# Sensor_Box_PWR_DC.net
KiCad netlist of a schematic drawn in Altium Designer
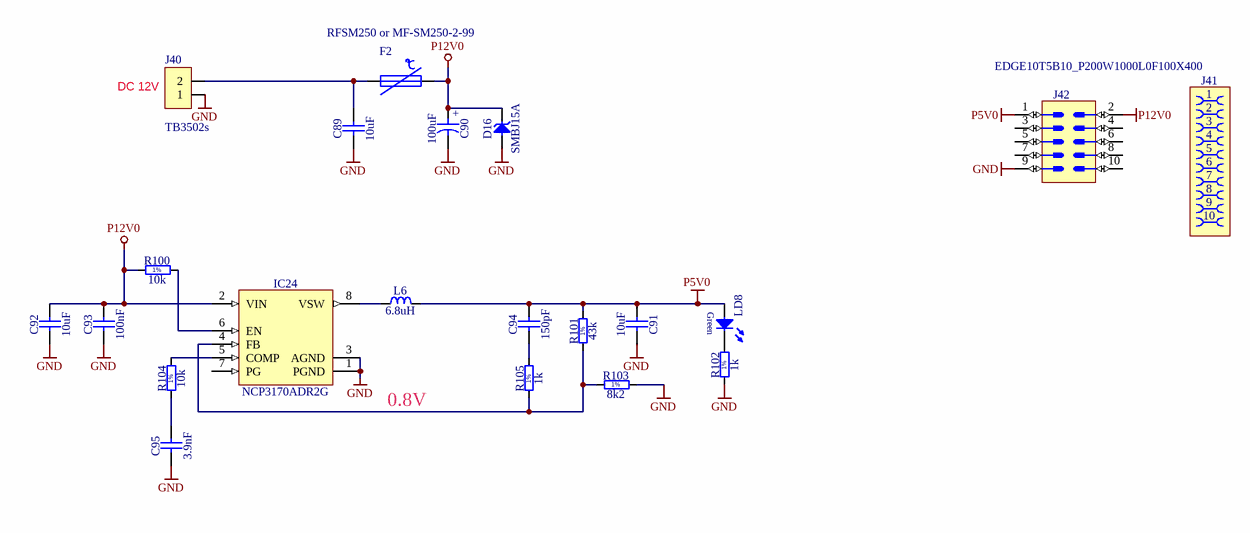
[diagram p0: Sensor_Box_PWR_DC.SchDoc]

(export (version "E")
  (design (tool "Eeschema 10.0.6"))
  (components
    (comp (ref "C89")
      (value "10uF")
      (footprint "CAPC2012X135N")
      (description "Non-polarised capacitor")
      (fields
        (field (name "PART NUMBER") "CC0805_10UF_16V_10%_X5R")
        (field (name "VOLTAGE") "16V")
        (field (name "AUTHOR") "CERN DEM JLC")
      )
      (libsource (lib "Capacitors") (part "Capacitor - non polarized"))
    )
    (comp (ref "C90")
      (value "100uF")
      (footprint "CAPAE660X540N")
      (description "Polarised capacitor")
      (fields
        (field (name "PART NUMBER") "CAE660-540_100UF_16V_20%")
        (field (name "VOLTAGE") "16V")
        (field (name "AUTHOR") "CERN DEM JLC")
      )
      (libsource (lib "Capacitors") (part "Capacitor - polarized"))
    )
    (comp (ref "C91")
      (value "10uF")
      (footprint "CAPC2012X135N")
      (description "Non-polarised capacitor")
      (fields
        (field (name "PART NUMBER") "CC0805_10UF_16V_10%_X5R")
        (field (name "VOLTAGE") "16V")
        (field (name "AUTHOR") "CERN DEM JLC")
      )
      (libsource (lib "Capacitors") (part "Capacitor - non polarized"))
    )
    (comp (ref "C92")
      (value "10uF")
      (footprint "CAPC2012X135N")
      (description "Non-polarised capacitor")
      (fields
        (field (name "PART NUMBER") "CC0805_10UF_16V_10%_X5R")
        (field (name "VOLTAGE") "16V")
        (field (name "AUTHOR") "CERN DEM JLC")
      )
      (libsource (lib "Capacitors") (part "Capacitor - non polarized"))
    )
    (comp (ref "C93")
      (value "100nF")
      (footprint "CAPC1005X55N")
      (description "Non-polarised capacitor")
      (fields
        (field (name "PART NUMBER") "CC0402_100NF_16V_10%_X5R")
        (field (name "VOLTAGE") "16V")
        (field (name "AUTHOR") "CERN DEM JLC")
      )
      (libsource (lib "Capacitors") (part "Capacitor - non polarized"))
    )
    (comp (ref "C94")
      (value "150pF")
      (footprint "CAPC1608X87N")
      (description "Non-polarised capacitor")
      (fields
        (field (name "PART NUMBER") "CC0603_150PF_50V_1%_NP0")
        (field (name "VOLTAGE") "50V")
        (field (name "AUTHOR") "CERN DEM MR")
      )
      (libsource (lib "Capacitors") (part "Capacitor - non polarized"))
    )
    (comp (ref "C95")
      (value "3.9nF")
      (footprint "CAPC1608X87N")
      (description "Non-polarised capacitor")
      (fields
        (field (name "PART NUMBER") "CC0603_3.9NF_50V_5%_X7R")
        (field (name "VOLTAGE") "50V")
        (field (name "AUTHOR") "CERN DEM JLC")
      )
      (libsource (lib "Capacitors") (part "Capacitor - non polarized"))
    )
    (comp (ref "D16")
      (value "SMBJ15A")
      (footprint "DIOM5336X265N")
      (description "Zener Diode")
      (fields
        (field (name "VOLTAGE") "15V")
        (field (name "POWER") "600W")
        (field (name "AUTHOR") "CERN DEM JLC")
      )
      (libsource (lib "ICs And Semiconductors") (part "Diode Zener"))
    )
    (comp (ref "F2")
      (value "RFSM250 or MF-SM250-2-99")
      (footprint "SMD150-2")
      (description "2.50A/15V")
      (libsource (lib "LIBRARY_SCH") (part "F_PTC_9.5x6mm"))
    )
    (comp (ref "IC24")
      (value "NCP3170ADR2G")
      (footprint "SOIC127P600X175-8N")
      (description "Synchronous PWM Switching Converter")
      (fields (field (name "MANUFACTURER") "ON SEMICONDUCTOR") (field (name "AUTHOR") "CERN DEM MR"))
      (libsource (lib "ICs And Semiconductors") (part "NCP3170ADR2G"))
    )
    (comp (ref "J40")
      (value "TB3502s")
      (footprint "tbx3502s")
      (description "Terminal Block")
      (libsource (lib "LIBRARY_SCH") (part "CON_TB2"))
    )
    (comp (ref "J41")
      (value "~")
      (footprint "AVX_00 9159 010 061 916")
      (description "Open Ended Card Edge Connector, 9159 Series")
      (fields
        (field (name "PART NUMBER") "AVX_00 9159 010 061 916")
        (field (name "MANUFACTURER") "AVX")
        (field (name "AUTHOR") "CERN DEM MR")
      )
      (libsource (lib "Connectors") (part "AVX_00 9159 010 061 916"))
    )
    (comp (ref "J42")
      (value "~")
      (footprint "EDGE10T5B10_P200W1000L0F100X400")
      (description "PCB Edge Connector 10 (2x5)")
      (fields
        (field (name "PART NUMBER") "EDGE10T5B10_P200W1000L0F100X400")
        (field (name "AUTHOR") "CERN DEM MR")
      )
      (libsource (lib "Connectors") (part "PCB Edge Connector 10 (2x5)"))
    )
    (comp (ref "L6")
      (value "6.8uH")
      (footprint "IND_BOURNS_SRU8043")
      (description "Inductor")
      (fields
        (field (name "PART NUMBER") "IND_6.8UH_30%_BOURNS_SRU8043")
        (field (name "POWER") "3.8A")
        (field (name "AUTHOR") "CERN DEM JMW")
      )
      (libsource (lib "Inductors & Transformers") (part "Inductor"))
    )
    (comp (ref "LD8")
      (value "Green")
      (footprint "LED_KINGBRIGHT_KPTR3216")
      (description "LED Green 1A 2C")
      (fields
        (field (name "PART NUMBER") "LED_KINGBRIGHT_KPTR-3216CGCK")
        (field (name "MANUFACTURER") "KINGBRIGHT")
        (field (name "AUTHOR") "CERN DEM MR")
      )
      (libsource (lib "ICs And Semiconductors") (part "LED_KINGBRIGHT_KPTR-3216CGCK"))
    )
    (comp (ref "R100")
      (value "10k")
      (footprint "RESC1005X40N")
      (description "Resistor - 1%")
      (fields
        (field (name "PART NUMBER") "R0402_10K_1%_0.0625W_100PPM")
        (field (name "POWER") "0.0625W")
        (field (name "AUTHOR") "CERN DEM JLC")
      )
      (libsource (lib "Resistors") (part "Resistor - 1%"))
    )
    (comp (ref "R101")
      (value "43k")
      (footprint "RESC1608X55N")
      (description "Resistor - 1%")
      (fields
        (field (name "PART NUMBER") "R0603_43K_1%_0.1W_100PPM")
        (field (name "POWER") "0.1W")
        (field (name "AUTHOR") "CERN DEM JLC")
      )
      (libsource (lib "Resistors") (part "Resistor - 1%"))
    )
    (comp (ref "R102")
      (value "1k")
      (footprint "RESC1005X40N")
      (description "Resistor - 1%")
      (fields
        (field (name "PART NUMBER") "R0402_1K_1%_0.0625W_100PPM")
        (field (name "POWER") "0.0625W")
        (field (name "AUTHOR") "CERN DEM JLC")
      )
      (libsource (lib "Resistors") (part "Resistor - 1%"))
    )
    (comp (ref "R103")
      (value "8k2")
      (footprint "RESC1608X55N")
      (description "Resistor - 1%")
      (fields
        (field (name "PART NUMBER") "R0603_8K2_1%_0.1W_100PPM")
        (field (name "POWER") "0.1W")
        (field (name "AUTHOR") "CERN DEM JLC")
      )
      (libsource (lib "Resistors") (part "Resistor - 1%"))
    )
    (comp (ref "R104")
      (value "10k")
      (footprint "RESC1005X40N")
      (description "Resistor - 1%")
      (fields
        (field (name "PART NUMBER") "R0402_10K_1%_0.0625W_100PPM")
        (field (name "POWER") "0.0625W")
        (field (name "AUTHOR") "CERN DEM JLC")
      )
      (libsource (lib "Resistors") (part "Resistor - 1%"))
    )
    (comp (ref "R105")
      (value "1k")
      (footprint "RESC1005X40N")
      (description "Resistor - 1%")
      (fields
        (field (name "PART NUMBER") "R0402_1K_1%_0.0625W_100PPM")
        (field (name "POWER") "0.0625W")
        (field (name "AUTHOR") "CERN DEM JLC")
      )
      (libsource (lib "Resistors") (part "Resistor - 1%"))
    )
  )
  (nets
    (net (code "1") (name "GND") (class "Default")
      (node (ref "C89") (pin "1") (pinfunction "1_1") (pintype "passive"))
      (node (ref "C90") (pin "2") (pinfunction "2_2") (pintype "passive"))
      (node (ref "C91") (pin "2") (pinfunction "2_2") (pintype "passive"))
      (node (ref "C92") (pin "1") (pinfunction "1_1") (pintype "passive"))
      (node (ref "C93") (pin "1") (pinfunction "1_1") (pintype "passive"))
      (node (ref "C95") (pin "1") (pinfunction "1_1") (pintype "passive"))
      (node (ref "D16") (pin "2") (pinfunction "A_2") (pintype "passive"))
      (node (ref "IC24") (pin "1") (pinfunction "PGND_1") (pintype "power_in"))
      (node (ref "IC24") (pin "3") (pinfunction "AGND_3") (pintype "power_in"))
      (node (ref "J40") (pin "1") (pinfunction "1_1") (pintype "passive"))
      (node (ref "J42") (pin "9") (pinfunction "9_9") (pintype "bidirectional"))
      (node (ref "R102") (pin "1") (pinfunction "1_1") (pintype "passive"))
      (node (ref "R103") (pin "2") (pinfunction "2_2") (pintype "passive"))
    )
    (net (code "2") (name "Net-(C89-Pad2)") (class "Default")
      (node (ref "C89") (pin "2") (pinfunction "2_2") (pintype "passive"))
      (node (ref "F2") (pin "1") (pinfunction "1_1") (pintype "passive"))
      (node (ref "J40") (pin "2") (pinfunction "2_2") (pintype "passive"))
    )
    (net (code "3") (name "Net-(C94-Pad1)") (class "Default")
      (node (ref "C94") (pin "1") (pinfunction "1_1") (pintype "passive"))
      (node (ref "R105") (pin "2") (pinfunction "2_2") (pintype "passive"))
    )
    (net (code "4") (name "Net-(C95-Pad2)") (class "Default")
      (node (ref "C95") (pin "2") (pinfunction "2_2") (pintype "passive"))
      (node (ref "R104") (pin "1") (pinfunction "1_1") (pintype "passive"))
    )
    (net (code "5") (name "Net-(IC24-COMP)") (class "Default")
      (node (ref "IC24") (pin "5") (pinfunction "COMP_5") (pintype "input"))
      (node (ref "R104") (pin "2") (pinfunction "2_2") (pintype "passive"))
    )
    (net (code "6") (name "Net-(IC24-EN)") (class "Default")
      (node (ref "IC24") (pin "6") (pinfunction "EN_6") (pintype "input"))
      (node (ref "R100") (pin "2") (pinfunction "2_2") (pintype "passive"))
    )
    (net (code "7") (name "Net-(IC24-FB)") (class "Default")
      (node (ref "IC24") (pin "4") (pinfunction "FB_4") (pintype "input"))
      (node (ref "R101") (pin "1") (pinfunction "1_1") (pintype "passive"))
      (node (ref "R103") (pin "1") (pinfunction "1_1") (pintype "passive"))
      (node (ref "R105") (pin "1") (pinfunction "1_1") (pintype "passive"))
    )
    (net (code "8") (name "Net-(IC24-VSW)") (class "Default")
      (node (ref "IC24") (pin "8") (pinfunction "VSW_8") (pintype "output"))
      (node (ref "L6") (pin "1") (pinfunction "1_1") (pintype "passive"))
    )
    (net (code "9") (name "Net-(LD8-C)") (class "Default")
      (node (ref "LD8") (pin "1") (pinfunction "C_1") (pintype "passive"))
      (node (ref "R102") (pin "2") (pinfunction "2_2") (pintype "passive"))
    )
    (net (code "10") (name "P5V0") (class "Default")
      (node (ref "C91") (pin "1") (pinfunction "1_1") (pintype "passive"))
      (node (ref "C94") (pin "2") (pinfunction "2_2") (pintype "passive"))
      (node (ref "J42") (pin "1") (pinfunction "1_1") (pintype "bidirectional"))
      (node (ref "L6") (pin "2") (pinfunction "2_2") (pintype "passive"))
      (node (ref "LD8") (pin "2") (pinfunction "A_2") (pintype "passive"))
      (node (ref "R101") (pin "2") (pinfunction "2_2") (pintype "passive"))
    )
    (net (code "11") (name "P12V0") (class "Default")
      (node (ref "C90") (pin "1") (pinfunction "1_1") (pintype "passive"))
      (node (ref "C92") (pin "2") (pinfunction "2_2") (pintype "passive"))
      (node (ref "C93") (pin "2") (pinfunction "2_2") (pintype "passive"))
      (node (ref "D16") (pin "1") (pinfunction "C_1") (pintype "passive"))
      (node (ref "F2") (pin "2") (pinfunction "2_2") (pintype "passive"))
      (node (ref "IC24") (pin "2") (pinfunction "VIN_2") (pintype "input"))
      (node (ref "J42") (pin "2") (pinfunction "2_2") (pintype "bidirectional"))
      (node (ref "R100") (pin "1") (pinfunction "1_1") (pintype "passive"))
    )
    (net (code "12") (name "unconnected-(IC24-PG-Pad7)") (class "Default")
      (node (ref "IC24") (pin "7") (pinfunction "PG_7") (pintype "input"))
    )
    (net (code "13") (name "unconnected-(J42-Pad3)") (class "Default")
      (node (ref "J42") (pin "3") (pinfunction "3_3") (pintype "bidirectional"))
    )
    (net (code "14") (name "unconnected-(J42-Pad4)") (class "Default")
      (node (ref "J42") (pin "4") (pinfunction "4_4") (pintype "bidirectional"))
    )
    (net (code "15") (name "unconnected-(J42-Pad5)") (class "Default")
      (node (ref "J42") (pin "5") (pinfunction "5_5") (pintype "bidirectional"))
    )
    (net (code "16") (name "unconnected-(J42-Pad6)") (class "Default")
      (node (ref "J42") (pin "6") (pinfunction "6_6") (pintype "bidirectional"))
    )
    (net (code "17") (name "unconnected-(J42-Pad7)") (class "Default")
      (node (ref "J42") (pin "7") (pinfunction "7_7") (pintype "bidirectional"))
    )
    (net (code "18") (name "unconnected-(J42-Pad8)") (class "Default")
      (node (ref "J42") (pin "8") (pinfunction "8_8") (pintype "bidirectional"))
    )
    (net (code "19") (name "unconnected-(J42-Pad10)") (class "Default")
      (node (ref "J42") (pin "10") (pinfunction "10_10") (pintype "bidirectional"))
    )
  )
)
